# Ext_Sense_board.net
KiCad netlist of a schematic drawn in EAGLE
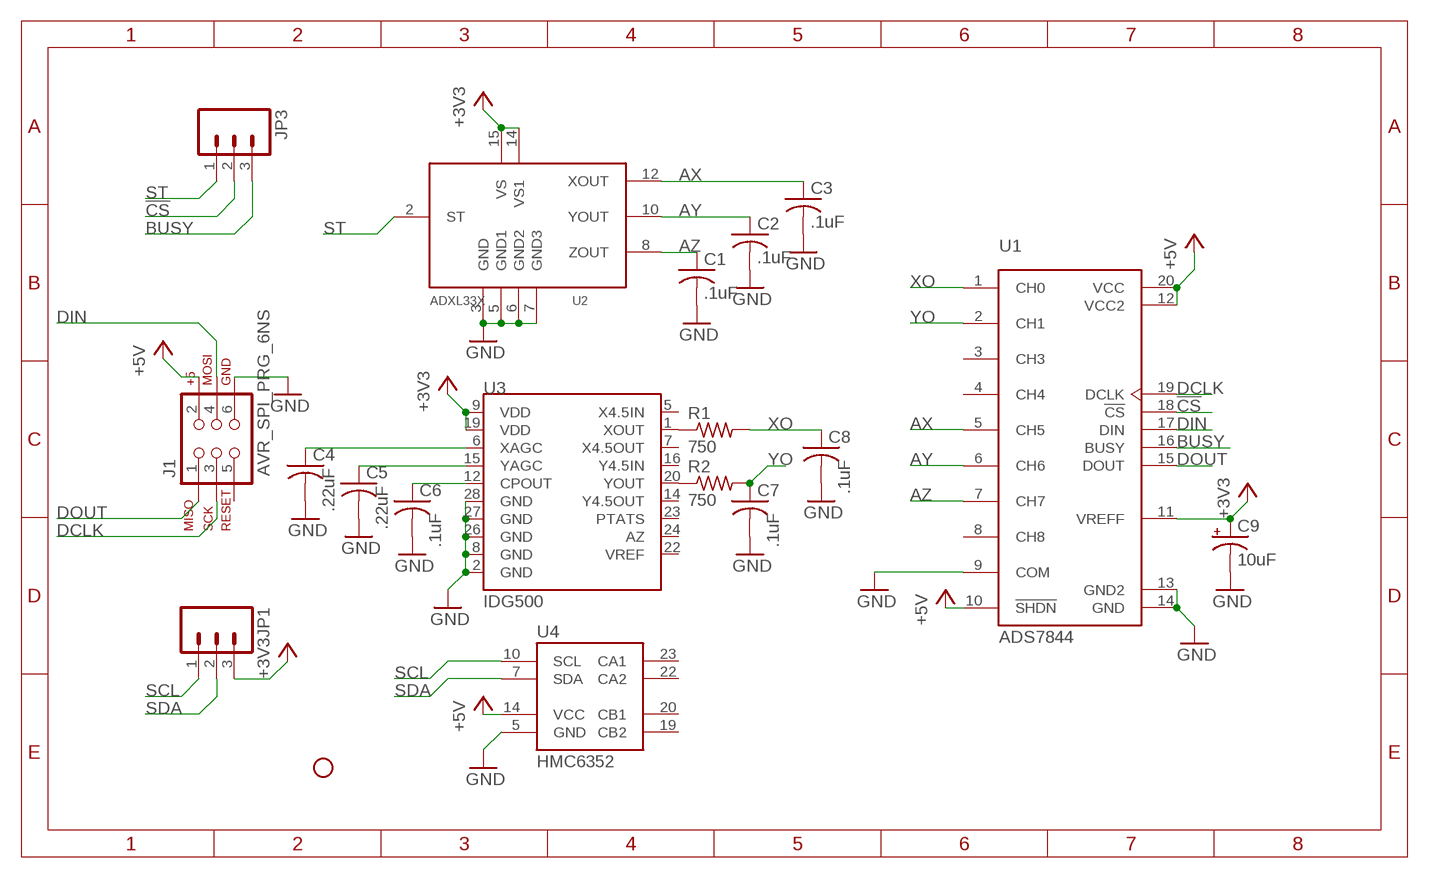
[diagram p0: schematic, sheet 1]

(export (version "E")
  (design (tool "Eeschema 10.0.6"))
  (components
    (comp (ref "C1")
      (value ".1uF")
      (footprint "eagle-import:C0805")
      (libsource (lib "eagle-import") (part "C-USC0805"))
    )
    (comp (ref "C2")
      (value ".1uF")
      (footprint "eagle-import:C0805")
      (libsource (lib "eagle-import") (part "C-USC0805"))
    )
    (comp (ref "C3")
      (value ".1uF")
      (footprint "eagle-import:C0805")
      (libsource (lib "eagle-import") (part "C-USC0805"))
    )
    (comp (ref "C4")
      (value ".22uF")
      (footprint "eagle-import:C0805")
      (libsource (lib "eagle-import") (part "C-USC0805"))
    )
    (comp (ref "C5")
      (value ".22uF")
      (footprint "eagle-import:C0805")
      (libsource (lib "eagle-import") (part "C-USC0805"))
    )
    (comp (ref "C6")
      (value ".1uF")
      (footprint "eagle-import:C0805")
      (libsource (lib "eagle-import") (part "C-USC0805"))
    )
    (comp (ref "C7")
      (value ".1uF")
      (footprint "eagle-import:C0805")
      (libsource (lib "eagle-import") (part "C-USC0805"))
    )
    (comp (ref "C8")
      (value ".1uF")
      (footprint "eagle-import:C0805")
      (libsource (lib "eagle-import") (part "C-USC0805"))
    )
    (comp (ref "C9")
      (value "10uF")
      (footprint "eagle-import:POLC1206")
      (libsource (lib "eagle-import") (part "POLCAP"))
    )
    (comp (ref "J1")
      (value "AVR_SPI_PRG_6NS")
      (footprint "eagle-import:2X3-NS")
      (libsource (lib "eagle-import") (part "AVR_SPI_PRG_6NS"))
    )
    (comp (ref "JP1")
      (value "M031X03_NO_SILK")
      (footprint "eagle-import:1X03_NO_SILK")
      (libsource (lib "eagle-import") (part "M031X03_NO_SILK"))
    )
    (comp (ref "JP2")
      (value "STAND-OFF")
      (footprint "eagle-import:STAND-OFF")
      (libsource (lib "eagle-import") (part "STAND-OFF"))
    )
    (comp (ref "JP3")
      (value "M031X03_NO_SILK")
      (footprint "eagle-import:1X03_NO_SILK")
      (libsource (lib "eagle-import") (part "M031X03_NO_SILK"))
    )
    (comp (ref "R1")
      (value "750")
      (footprint "eagle-import:R0805")
      (libsource (lib "eagle-import") (part "R-US_R0805"))
    )
    (comp (ref "R2")
      (value "750")
      (footprint "eagle-import:R0805")
      (libsource (lib "eagle-import") (part "R-US_R0805"))
    )
    (comp (ref "U1")
      (value "ADS7844")
      (footprint "eagle-import:SSOP-20")
      (libsource (lib "eagle-import") (part "ADS7844"))
    )
    (comp (ref "U2")
      (value "ADXL33X")
      (footprint "eagle-import:16LCSP")
      (libsource (lib "eagle-import") (part "ADXL33X"))
    )
    (comp (ref "U3")
      (value "IDG500")
      (footprint "eagle-import:SPARKFUN_IDG500")
      (libsource (lib "eagle-import") (part "IDG500"))
    )
    (comp (ref "U4")
      (value "HMC6352")
      (footprint "eagle-import:LCC24")
      (libsource (lib "eagle-import") (part "HMC6352"))
    )
  )
  (nets
    (net (code "1") (name "+3V3") (class "Default")
      (node (ref "C9") (pin "1") (pinfunction "+_1") (pintype "passive"))
      (node (ref "JP1") (pin "3") (pinfunction "3_3") (pintype "passive"))
      (node (ref "U1") (pin "11") (pinfunction "VREFF_11") (pintype "bidirectional"))
      (node (ref "U2") (pin "14") (pinfunction "VS1_14") (pintype "power_in"))
      (node (ref "U2") (pin "15") (pinfunction "VS_15") (pintype "power_in"))
      (node (ref "U3") (pin "19") (pinfunction "VDD_19") (pintype "bidirectional"))
      (node (ref "U3") (pin "9") (pinfunction "VDD_9") (pintype "bidirectional"))
    )
    (net (code "2") (name "+5V") (class "Default")
      (node (ref "J1") (pin "2") (pinfunction "2_2") (pintype "passive"))
      (node (ref "U1") (pin "10") (pinfunction "~{SHDN}_10") (pintype "bidirectional"))
      (node (ref "U1") (pin "12") (pinfunction "VCC2_12") (pintype "bidirectional"))
      (node (ref "U1") (pin "20") (pinfunction "VCC_20") (pintype "bidirectional"))
      (node (ref "U4") (pin "14") (pinfunction "VCC_14") (pintype "bidirectional"))
    )
    (net (code "3") (name "/AX") (class "Default")
      (node (ref "C3") (pin "1") (pinfunction "1_1") (pintype "passive"))
      (node (ref "U1") (pin "5") (pinfunction "CH5_5") (pintype "bidirectional"))
      (node (ref "U2") (pin "12") (pinfunction "XOUT_12") (pintype "output"))
    )
    (net (code "4") (name "/AY") (class "Default")
      (node (ref "C2") (pin "1") (pinfunction "1_1") (pintype "passive"))
      (node (ref "U1") (pin "6") (pinfunction "CH6_6") (pintype "bidirectional"))
      (node (ref "U2") (pin "10") (pinfunction "YOUT_10") (pintype "output"))
    )
    (net (code "5") (name "/AZ") (class "Default")
      (node (ref "C1") (pin "1") (pinfunction "1_1") (pintype "passive"))
      (node (ref "U1") (pin "7") (pinfunction "CH7_7") (pintype "bidirectional"))
      (node (ref "U2") (pin "8") (pinfunction "ZOUT_8") (pintype "output"))
    )
    (net (code "6") (name "/BUSY") (class "Default")
      (node (ref "JP3") (pin "3") (pinfunction "3_3") (pintype "passive"))
      (node (ref "U1") (pin "16") (pinfunction "BUSY_16") (pintype "bidirectional"))
    )
    (net (code "7") (name "/DCLK") (class "Default")
      (node (ref "J1") (pin "3") (pinfunction "3_3") (pintype "passive"))
      (node (ref "U1") (pin "19") (pinfunction "DCLK_19") (pintype "bidirectional"))
    )
    (net (code "8") (name "/DIN") (class "Default")
      (node (ref "J1") (pin "4") (pinfunction "4_4") (pintype "passive"))
      (node (ref "U1") (pin "17") (pinfunction "DIN_17") (pintype "bidirectional"))
    )
    (net (code "9") (name "/DOUT") (class "Default")
      (node (ref "J1") (pin "1") (pinfunction "1_1") (pintype "passive"))
      (node (ref "U1") (pin "15") (pinfunction "DOUT_15") (pintype "bidirectional"))
    )
    (net (code "10") (name "/SCL") (class "Default")
      (node (ref "JP1") (pin "1") (pinfunction "1_1") (pintype "passive"))
      (node (ref "U4") (pin "10") (pinfunction "SCL_10") (pintype "bidirectional"))
    )
    (net (code "11") (name "/SDA") (class "Default")
      (node (ref "JP1") (pin "2") (pinfunction "2_2") (pintype "passive"))
      (node (ref "U4") (pin "7") (pinfunction "SDA_7") (pintype "bidirectional"))
    )
    (net (code "12") (name "/ST") (class "Default")
      (node (ref "JP3") (pin "1") (pinfunction "1_1") (pintype "passive"))
      (node (ref "U2") (pin "2") (pinfunction "ST_2") (pintype "input"))
    )
    (net (code "13") (name "/XO") (class "Default")
      (node (ref "C8") (pin "1") (pinfunction "1_1") (pintype "passive"))
      (node (ref "R1") (pin "2") (pinfunction "2_2") (pintype "passive"))
      (node (ref "U1") (pin "1") (pinfunction "CH0_1") (pintype "bidirectional"))
    )
    (net (code "14") (name "/YO") (class "Default")
      (node (ref "C7") (pin "1") (pinfunction "1_1") (pintype "passive"))
      (node (ref "R2") (pin "2") (pinfunction "2_2") (pintype "passive"))
      (node (ref "U1") (pin "2") (pinfunction "CH1_2") (pintype "bidirectional"))
    )
    (net (code "15") (name "/~{CS}") (class "Default")
      (node (ref "JP3") (pin "2") (pinfunction "2_2") (pintype "passive"))
      (node (ref "U1") (pin "18") (pinfunction "~{CS}_18") (pintype "bidirectional"))
    )
    (net (code "16") (name "GND") (class "Default")
      (node (ref "C1") (pin "2") (pinfunction "2_2") (pintype "passive"))
      (node (ref "C2") (pin "2") (pinfunction "2_2") (pintype "passive"))
      (node (ref "C3") (pin "2") (pinfunction "2_2") (pintype "passive"))
      (node (ref "C4") (pin "2") (pinfunction "2_2") (pintype "passive"))
      (node (ref "C5") (pin "2") (pinfunction "2_2") (pintype "passive"))
      (node (ref "C6") (pin "2") (pinfunction "2_2") (pintype "passive"))
      (node (ref "C7") (pin "2") (pinfunction "2_2") (pintype "passive"))
      (node (ref "C8") (pin "2") (pinfunction "2_2") (pintype "passive"))
      (node (ref "C9") (pin "2") (pinfunction "-_2") (pintype "passive"))
      (node (ref "J1") (pin "6") (pinfunction "6_6") (pintype "passive"))
      (node (ref "U1") (pin "13") (pinfunction "GND2_13") (pintype "bidirectional"))
      (node (ref "U1") (pin "14") (pinfunction "GND_14") (pintype "bidirectional"))
      (node (ref "U1") (pin "9") (pinfunction "COM_9") (pintype "bidirectional"))
      (node (ref "U2") (pin "3") (pinfunction "GND_3") (pintype "power_in"))
      (node (ref "U2") (pin "5") (pinfunction "GND1_5") (pintype "power_in"))
      (node (ref "U2") (pin "6") (pinfunction "GND2_6") (pintype "power_in"))
      (node (ref "U2") (pin "7") (pinfunction "GND3_7") (pintype "power_in"))
      (node (ref "U3") (pin "2") (pinfunction "GND_2") (pintype "bidirectional"))
      (node (ref "U3") (pin "26") (pinfunction "GND_26") (pintype "bidirectional"))
      (node (ref "U3") (pin "27") (pinfunction "GND_27") (pintype "bidirectional"))
      (node (ref "U3") (pin "28") (pinfunction "GND_28") (pintype "bidirectional"))
      (node (ref "U3") (pin "8") (pinfunction "GND_8") (pintype "bidirectional"))
      (node (ref "U4") (pin "5") (pinfunction "GND_5") (pintype "bidirectional"))
    )
    (net (code "17") (name "Net-(U3-CPOUT)") (class "Default")
      (node (ref "C6") (pin "1") (pinfunction "1_1") (pintype "passive"))
      (node (ref "U3") (pin "12") (pinfunction "CPOUT_12") (pintype "bidirectional"))
    )
    (net (code "18") (name "Net-(U3-XAGC)") (class "Default")
      (node (ref "C4") (pin "1") (pinfunction "1_1") (pintype "passive"))
      (node (ref "U3") (pin "6") (pinfunction "XAGC_6") (pintype "bidirectional"))
    )
    (net (code "19") (name "Net-(U3-XOUT)") (class "Default")
      (node (ref "R1") (pin "1") (pinfunction "1_1") (pintype "passive"))
      (node (ref "U3") (pin "1") (pinfunction "XOUT_1") (pintype "bidirectional"))
    )
    (net (code "20") (name "Net-(U3-YAGC)") (class "Default")
      (node (ref "C5") (pin "1") (pinfunction "1_1") (pintype "passive"))
      (node (ref "U3") (pin "15") (pinfunction "YAGC_15") (pintype "bidirectional"))
    )
    (net (code "21") (name "Net-(U3-YOUT)") (class "Default")
      (node (ref "R2") (pin "1") (pinfunction "1_1") (pintype "passive"))
      (node (ref "U3") (pin "20") (pinfunction "YOUT_20") (pintype "bidirectional"))
    )
    (net (code "22") (name "unconnected-(J1-Pad5)") (class "Default")
      (node (ref "J1") (pin "5") (pinfunction "5_5") (pintype "passive"))
    )
    (net (code "23") (name "unconnected-(U1-CH3-Pad3)") (class "Default")
      (node (ref "U1") (pin "3") (pinfunction "CH3_3") (pintype "bidirectional"))
    )
    (net (code "24") (name "unconnected-(U1-CH4-Pad4)") (class "Default")
      (node (ref "U1") (pin "4") (pinfunction "CH4_4") (pintype "bidirectional"))
    )
    (net (code "25") (name "unconnected-(U1-CH8-Pad8)") (class "Default")
      (node (ref "U1") (pin "8") (pinfunction "CH8_8") (pintype "bidirectional"))
    )
    (net (code "26") (name "unconnected-(U3-AZ-Pad24)") (class "Default")
      (node (ref "U3") (pin "24") (pinfunction "AZ_24") (pintype "bidirectional"))
    )
    (net (code "27") (name "unconnected-(U3-PTATS-Pad23)") (class "Default")
      (node (ref "U3") (pin "23") (pinfunction "PTATS_23") (pintype "bidirectional"))
    )
    (net (code "28") (name "unconnected-(U3-VREF-Pad22)") (class "Default")
      (node (ref "U3") (pin "22") (pinfunction "VREF_22") (pintype "bidirectional"))
    )
    (net (code "29") (name "unconnected-(U3-X4.5IN-Pad5)") (class "Default")
      (node (ref "U3") (pin "5") (pinfunction "X4.5IN_5") (pintype "bidirectional"))
    )
    (net (code "30") (name "unconnected-(U3-X4.5OUT-Pad7)") (class "Default")
      (node (ref "U3") (pin "7") (pinfunction "X4.5OUT_7") (pintype "bidirectional"))
    )
    (net (code "31") (name "unconnected-(U3-Y4.5IN-Pad16)") (class "Default")
      (node (ref "U3") (pin "16") (pinfunction "Y4.5IN_16") (pintype "bidirectional"))
    )
    (net (code "32") (name "unconnected-(U3-Y4.5OUT-Pad14)") (class "Default")
      (node (ref "U3") (pin "14") (pinfunction "Y4.5OUT_14") (pintype "bidirectional"))
    )
    (net (code "33") (name "unconnected-(U4-CA1-Pad23)") (class "Default")
      (node (ref "U4") (pin "23") (pinfunction "CA1_23") (pintype "bidirectional"))
    )
    (net (code "34") (name "unconnected-(U4-CA2-Pad22)") (class "Default")
      (node (ref "U4") (pin "22") (pinfunction "CA2_22") (pintype "bidirectional"))
    )
    (net (code "35") (name "unconnected-(U4-CB1-Pad20)") (class "Default")
      (node (ref "U4") (pin "20") (pinfunction "CB1_20") (pintype "bidirectional"))
    )
    (net (code "36") (name "unconnected-(U4-CB2-Pad19)") (class "Default")
      (node (ref "U4") (pin "19") (pinfunction "CB2_19") (pintype "bidirectional"))
    )
  )
)
